# HighVBoard_2_0.net
KiCad netlist of a schematic drawn in EAGLE
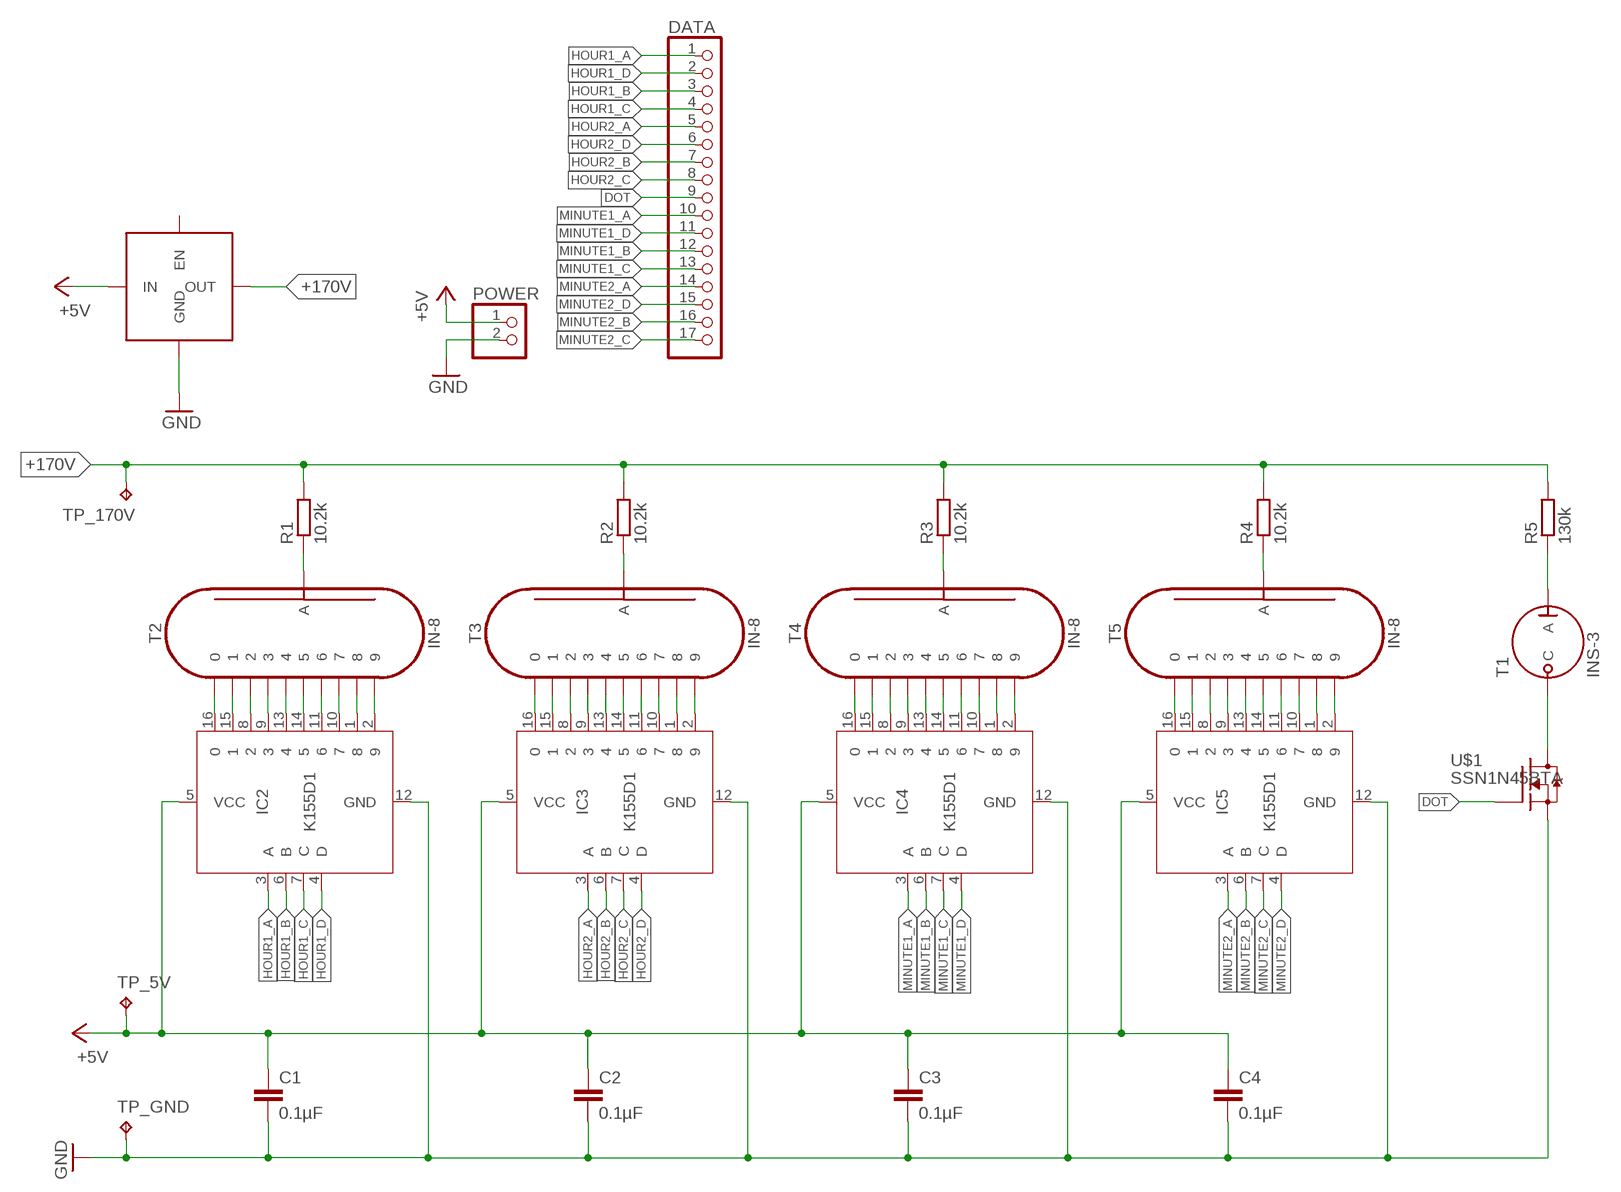
[diagram p0: schematic, sheet 1]

(export (version "E")
  (design (tool "Eeschema 10.0.6"))
  (components
    (comp (ref "C1")
      (value "0.1µF")
      (footprint "eagle-import:C025-024X044")
      (libsource (lib "eagle-import") (part "C-EU025-024X044"))
    )
    (comp (ref "C2")
      (value "0.1µF")
      (footprint "eagle-import:C025-024X044")
      (libsource (lib "eagle-import") (part "C-EU025-024X044"))
    )
    (comp (ref "C3")
      (value "0.1µF")
      (footprint "eagle-import:C025-024X044")
      (libsource (lib "eagle-import") (part "C-EU025-024X044"))
    )
    (comp (ref "C4")
      (value "0.1µF")
      (footprint "eagle-import:C025-024X044")
      (libsource (lib "eagle-import") (part "C-EU025-024X044"))
    )
    (comp (ref "DATA")
      (value "PINHD-1X17")
      (footprint "eagle-import:1X17")
      (libsource (lib "eagle-import") (part "PINHD-1X17"))
    )
    (comp (ref "IC2")
      (value "K155D1")
      (footprint "eagle-import:DIL16")
      (libsource (lib "eagle-import") (part "K155D1"))
    )
    (comp (ref "IC3")
      (value "K155D1")
      (footprint "eagle-import:DIL16")
      (libsource (lib "eagle-import") (part "K155D1"))
    )
    (comp (ref "IC4")
      (value "K155D1")
      (footprint "eagle-import:DIL16")
      (libsource (lib "eagle-import") (part "K155D1"))
    )
    (comp (ref "IC5")
      (value "K155D1")
      (footprint "eagle-import:DIL16")
      (libsource (lib "eagle-import") (part "K155D1"))
    )
    (comp (ref "POWER")
      (value "PINHD-1X2")
      (footprint "eagle-import:1X02")
      (libsource (lib "eagle-import") (part "PINHD-1X2"))
    )
    (comp (ref "R1")
      (value "10.2k")
      (footprint "eagle-import:0207_10")
      (libsource (lib "eagle-import") (part "R-EU_0207/10"))
    )
    (comp (ref "R2")
      (value "10.2k")
      (footprint "eagle-import:0207_10")
      (libsource (lib "eagle-import") (part "R-EU_0207/10"))
    )
    (comp (ref "R3")
      (value "10.2k")
      (footprint "eagle-import:0207_10")
      (libsource (lib "eagle-import") (part "R-EU_0207/10"))
    )
    (comp (ref "R4")
      (value "10.2k")
      (footprint "eagle-import:0207_10")
      (libsource (lib "eagle-import") (part "R-EU_0207/10"))
    )
    (comp (ref "R5")
      (value "130k")
      (footprint "eagle-import:0207_10")
      (libsource (lib "eagle-import") (part "R-EU_0207/10"))
    )
    (comp (ref "T1")
      (value "INS-3")
      (footprint "eagle-import:INS-3")
      (libsource (lib "eagle-import") (part "INS-3"))
    )
    (comp (ref "T2")
      (value "IN-8")
      (footprint "eagle-import:IN-8")
      (libsource (lib "eagle-import") (part "IN-8"))
    )
    (comp (ref "T3")
      (value "IN-8")
      (footprint "eagle-import:IN-8")
      (libsource (lib "eagle-import") (part "IN-8"))
    )
    (comp (ref "T4")
      (value "IN-8")
      (footprint "eagle-import:IN-8")
      (libsource (lib "eagle-import") (part "IN-8"))
    )
    (comp (ref "T5")
      (value "IN-8")
      (footprint "eagle-import:IN-8")
      (libsource (lib "eagle-import") (part "IN-8"))
    )
    (comp (ref "TP_5V")
      (value "TPPAD1-13")
      (footprint "eagle-import:P1-13")
      (libsource (lib "eagle-import") (part "TPPAD1-13"))
    )
    (comp (ref "TP_170V")
      (value "TPPAD1-13")
      (footprint "eagle-import:P1-13")
      (libsource (lib "eagle-import") (part "TPPAD1-13"))
    )
    (comp (ref "TP_GND")
      (value "TPPAD1-13")
      (footprint "eagle-import:P1-13")
      (libsource (lib "eagle-import") (part "TPPAD1-13"))
    )
    (comp (ref "U$1")
      (value "SSN1N45BTA")
      (footprint "eagle-import:TO92")
      (libsource (lib "eagle-import") (part "SSN1N45BTA"))
    )
    (comp (ref "U$2")
      (value "NIXIE-PSU")
      (footprint "eagle-import:NIXIE-PSU")
      (libsource (lib "eagle-import") (part "NIXIE-PSU"))
    )
  )
  (nets
    (net (code "1") (name "+5V") (class "Default")
      (node (ref "C1") (pin "1") (pinfunction "1_1") (pintype "passive"))
      (node (ref "C2") (pin "1") (pinfunction "1_1") (pintype "passive"))
      (node (ref "C3") (pin "1") (pinfunction "1_1") (pintype "passive"))
      (node (ref "C4") (pin "1") (pinfunction "1_1") (pintype "passive"))
      (node (ref "IC2") (pin "5") (pinfunction "VCC_5") (pintype "bidirectional"))
      (node (ref "IC3") (pin "5") (pinfunction "VCC_5") (pintype "bidirectional"))
      (node (ref "IC4") (pin "5") (pinfunction "VCC_5") (pintype "bidirectional"))
      (node (ref "IC5") (pin "5") (pinfunction "VCC_5") (pintype "bidirectional"))
      (node (ref "POWER") (pin "1") (pinfunction "1_1") (pintype "passive"))
      (node (ref "TP_5V") (pin "TP") (pinfunction "TP_TP") (pintype "input"))
      (node (ref "U$2") (pin "1") (pinfunction "IN_1") (pintype "bidirectional"))
    )
    (net (code "2") (name "+170V") (class "Default")
      (node (ref "R1") (pin "2") (pinfunction "2_2") (pintype "passive"))
      (node (ref "R2") (pin "2") (pinfunction "2_2") (pintype "passive"))
      (node (ref "R3") (pin "2") (pinfunction "2_2") (pintype "passive"))
      (node (ref "R4") (pin "2") (pinfunction "2_2") (pintype "passive"))
      (node (ref "R5") (pin "2") (pinfunction "2_2") (pintype "passive"))
      (node (ref "TP_170V") (pin "TP") (pinfunction "TP_TP") (pintype "input"))
      (node (ref "U$2") (pin "5") (pinfunction "OUT_5") (pintype "bidirectional"))
    )
    (net (code "3") (name "DOT") (class "Default")
      (node (ref "DATA") (pin "9") (pinfunction "9_9") (pintype "passive"))
      (node (ref "U$1") (pin "1") (pinfunction "G_1") (pintype "passive"))
    )
    (net (code "4") (name "GND") (class "Default")
      (node (ref "C1") (pin "2") (pinfunction "2_2") (pintype "passive"))
      (node (ref "C2") (pin "2") (pinfunction "2_2") (pintype "passive"))
      (node (ref "C3") (pin "2") (pinfunction "2_2") (pintype "passive"))
      (node (ref "C4") (pin "2") (pinfunction "2_2") (pintype "passive"))
      (node (ref "IC2") (pin "12") (pinfunction "GND_12") (pintype "bidirectional"))
      (node (ref "IC3") (pin "12") (pinfunction "GND_12") (pintype "bidirectional"))
      (node (ref "IC4") (pin "12") (pinfunction "GND_12") (pintype "bidirectional"))
      (node (ref "IC5") (pin "12") (pinfunction "GND_12") (pintype "bidirectional"))
      (node (ref "POWER") (pin "2") (pinfunction "2_2") (pintype "passive"))
      (node (ref "TP_GND") (pin "TP") (pinfunction "TP_TP") (pintype "input"))
      (node (ref "U$1") (pin "3") (pinfunction "S_3") (pintype "passive"))
      (node (ref "U$2") (pin "2") (pinfunction "GND_2") (pintype "bidirectional"))
      (node (ref "U$2") (pin "4") (pinfunction "GND_4") (pintype "bidirectional"))
    )
    (net (code "5") (name "HOUR1_A") (class "Default")
      (node (ref "DATA") (pin "1") (pinfunction "1_1") (pintype "passive"))
      (node (ref "IC2") (pin "3") (pinfunction "A_3") (pintype "bidirectional"))
    )
    (net (code "6") (name "HOUR1_B") (class "Default")
      (node (ref "DATA") (pin "3") (pinfunction "3_3") (pintype "passive"))
      (node (ref "IC2") (pin "6") (pinfunction "B_6") (pintype "bidirectional"))
    )
    (net (code "7") (name "HOUR1_C") (class "Default")
      (node (ref "DATA") (pin "4") (pinfunction "4_4") (pintype "passive"))
      (node (ref "IC2") (pin "7") (pinfunction "C_7") (pintype "bidirectional"))
    )
    (net (code "8") (name "HOUR1_D") (class "Default")
      (node (ref "DATA") (pin "2") (pinfunction "2_2") (pintype "passive"))
      (node (ref "IC2") (pin "4") (pinfunction "D_4") (pintype "bidirectional"))
    )
    (net (code "9") (name "HOUR2_A") (class "Default")
      (node (ref "DATA") (pin "5") (pinfunction "5_5") (pintype "passive"))
      (node (ref "IC3") (pin "3") (pinfunction "A_3") (pintype "bidirectional"))
    )
    (net (code "10") (name "HOUR2_B") (class "Default")
      (node (ref "DATA") (pin "7") (pinfunction "7_7") (pintype "passive"))
      (node (ref "IC3") (pin "6") (pinfunction "B_6") (pintype "bidirectional"))
    )
    (net (code "11") (name "HOUR2_C") (class "Default")
      (node (ref "DATA") (pin "8") (pinfunction "8_8") (pintype "passive"))
      (node (ref "IC3") (pin "7") (pinfunction "C_7") (pintype "bidirectional"))
    )
    (net (code "12") (name "HOUR2_D") (class "Default")
      (node (ref "DATA") (pin "6") (pinfunction "6_6") (pintype "passive"))
      (node (ref "IC3") (pin "4") (pinfunction "D_4") (pintype "bidirectional"))
    )
    (net (code "13") (name "MINUTE1_A") (class "Default")
      (node (ref "DATA") (pin "10") (pinfunction "10_10") (pintype "passive"))
      (node (ref "IC4") (pin "3") (pinfunction "A_3") (pintype "bidirectional"))
    )
    (net (code "14") (name "MINUTE1_B") (class "Default")
      (node (ref "DATA") (pin "12") (pinfunction "12_12") (pintype "passive"))
      (node (ref "IC4") (pin "6") (pinfunction "B_6") (pintype "bidirectional"))
    )
    (net (code "15") (name "MINUTE1_C") (class "Default")
      (node (ref "DATA") (pin "13") (pinfunction "13_13") (pintype "passive"))
      (node (ref "IC4") (pin "7") (pinfunction "C_7") (pintype "bidirectional"))
    )
    (net (code "16") (name "MINUTE1_D") (class "Default")
      (node (ref "DATA") (pin "11") (pinfunction "11_11") (pintype "passive"))
      (node (ref "IC4") (pin "4") (pinfunction "D_4") (pintype "bidirectional"))
    )
    (net (code "17") (name "MINUTE2_A") (class "Default")
      (node (ref "DATA") (pin "14") (pinfunction "14_14") (pintype "passive"))
      (node (ref "IC5") (pin "3") (pinfunction "A_3") (pintype "bidirectional"))
    )
    (net (code "18") (name "MINUTE2_B") (class "Default")
      (node (ref "DATA") (pin "16") (pinfunction "16_16") (pintype "passive"))
      (node (ref "IC5") (pin "6") (pinfunction "B_6") (pintype "bidirectional"))
    )
    (net (code "19") (name "MINUTE2_C") (class "Default")
      (node (ref "DATA") (pin "17") (pinfunction "17_17") (pintype "passive"))
      (node (ref "IC5") (pin "7") (pinfunction "C_7") (pintype "bidirectional"))
    )
    (net (code "20") (name "MINUTE2_D") (class "Default")
      (node (ref "DATA") (pin "15") (pinfunction "15_15") (pintype "passive"))
      (node (ref "IC5") (pin "4") (pinfunction "D_4") (pintype "bidirectional"))
    )
    (net (code "21") (name "Net-(IC2-0)") (class "Default")
      (node (ref "IC2") (pin "16") (pinfunction "0_16") (pintype "bidirectional"))
      (node (ref "T2") (pin "10") (pinfunction "0_10") (pintype "bidirectional"))
    )
    (net (code "22") (name "Net-(IC2-1)") (class "Default")
      (node (ref "IC2") (pin "15") (pinfunction "1_15") (pintype "bidirectional"))
      (node (ref "T2") (pin "1") (pinfunction "1_1") (pintype "bidirectional"))
    )
    (net (code "23") (name "Net-(IC2-2)") (class "Default")
      (node (ref "IC2") (pin "8") (pinfunction "2_8") (pintype "bidirectional"))
      (node (ref "T2") (pin "2") (pinfunction "2_2") (pintype "bidirectional"))
    )
    (net (code "24") (name "Net-(IC2-3)") (class "Default")
      (node (ref "IC2") (pin "9") (pinfunction "3_9") (pintype "bidirectional"))
      (node (ref "T2") (pin "3") (pinfunction "3_3") (pintype "bidirectional"))
    )
    (net (code "25") (name "Net-(IC2-4)") (class "Default")
      (node (ref "IC2") (pin "13") (pinfunction "4_13") (pintype "bidirectional"))
      (node (ref "T2") (pin "4") (pinfunction "4_4") (pintype "bidirectional"))
    )
    (net (code "26") (name "Net-(IC2-5)") (class "Default")
      (node (ref "IC2") (pin "14") (pinfunction "5_14") (pintype "bidirectional"))
      (node (ref "T2") (pin "5") (pinfunction "5_5") (pintype "bidirectional"))
    )
    (net (code "27") (name "Net-(IC2-6)") (class "Default")
      (node (ref "IC2") (pin "11") (pinfunction "6_11") (pintype "bidirectional"))
      (node (ref "T2") (pin "6") (pinfunction "6_6") (pintype "bidirectional"))
    )
    (net (code "28") (name "Net-(IC2-7)") (class "Default")
      (node (ref "IC2") (pin "10") (pinfunction "7_10") (pintype "bidirectional"))
      (node (ref "T2") (pin "7") (pinfunction "7_7") (pintype "bidirectional"))
    )
    (net (code "29") (name "Net-(IC2-8)") (class "Default")
      (node (ref "IC2") (pin "1") (pinfunction "8_1") (pintype "bidirectional"))
      (node (ref "T2") (pin "8") (pinfunction "8_8") (pintype "bidirectional"))
    )
    (net (code "30") (name "Net-(IC2-9)") (class "Default")
      (node (ref "IC2") (pin "2") (pinfunction "9_2") (pintype "bidirectional"))
      (node (ref "T2") (pin "9") (pinfunction "9_9") (pintype "bidirectional"))
    )
    (net (code "31") (name "Net-(IC3-0)") (class "Default")
      (node (ref "IC3") (pin "16") (pinfunction "0_16") (pintype "bidirectional"))
      (node (ref "T3") (pin "10") (pinfunction "0_10") (pintype "bidirectional"))
    )
    (net (code "32") (name "Net-(IC3-1)") (class "Default")
      (node (ref "IC3") (pin "15") (pinfunction "1_15") (pintype "bidirectional"))
      (node (ref "T3") (pin "1") (pinfunction "1_1") (pintype "bidirectional"))
    )
    (net (code "33") (name "Net-(IC3-2)") (class "Default")
      (node (ref "IC3") (pin "8") (pinfunction "2_8") (pintype "bidirectional"))
      (node (ref "T3") (pin "2") (pinfunction "2_2") (pintype "bidirectional"))
    )
    (net (code "34") (name "Net-(IC3-3)") (class "Default")
      (node (ref "IC3") (pin "9") (pinfunction "3_9") (pintype "bidirectional"))
      (node (ref "T3") (pin "3") (pinfunction "3_3") (pintype "bidirectional"))
    )
    (net (code "35") (name "Net-(IC3-4)") (class "Default")
      (node (ref "IC3") (pin "13") (pinfunction "4_13") (pintype "bidirectional"))
      (node (ref "T3") (pin "4") (pinfunction "4_4") (pintype "bidirectional"))
    )
    (net (code "36") (name "Net-(IC3-5)") (class "Default")
      (node (ref "IC3") (pin "14") (pinfunction "5_14") (pintype "bidirectional"))
      (node (ref "T3") (pin "5") (pinfunction "5_5") (pintype "bidirectional"))
    )
    (net (code "37") (name "Net-(IC3-6)") (class "Default")
      (node (ref "IC3") (pin "11") (pinfunction "6_11") (pintype "bidirectional"))
      (node (ref "T3") (pin "6") (pinfunction "6_6") (pintype "bidirectional"))
    )
    (net (code "38") (name "Net-(IC3-7)") (class "Default")
      (node (ref "IC3") (pin "10") (pinfunction "7_10") (pintype "bidirectional"))
      (node (ref "T3") (pin "7") (pinfunction "7_7") (pintype "bidirectional"))
    )
    (net (code "39") (name "Net-(IC3-8)") (class "Default")
      (node (ref "IC3") (pin "1") (pinfunction "8_1") (pintype "bidirectional"))
      (node (ref "T3") (pin "8") (pinfunction "8_8") (pintype "bidirectional"))
    )
    (net (code "40") (name "Net-(IC3-9)") (class "Default")
      (node (ref "IC3") (pin "2") (pinfunction "9_2") (pintype "bidirectional"))
      (node (ref "T3") (pin "9") (pinfunction "9_9") (pintype "bidirectional"))
    )
    (net (code "41") (name "Net-(IC4-0)") (class "Default")
      (node (ref "IC4") (pin "16") (pinfunction "0_16") (pintype "bidirectional"))
      (node (ref "T4") (pin "10") (pinfunction "0_10") (pintype "bidirectional"))
    )
    (net (code "42") (name "Net-(IC4-1)") (class "Default")
      (node (ref "IC4") (pin "15") (pinfunction "1_15") (pintype "bidirectional"))
      (node (ref "T4") (pin "1") (pinfunction "1_1") (pintype "bidirectional"))
    )
    (net (code "43") (name "Net-(IC4-2)") (class "Default")
      (node (ref "IC4") (pin "8") (pinfunction "2_8") (pintype "bidirectional"))
      (node (ref "T4") (pin "2") (pinfunction "2_2") (pintype "bidirectional"))
    )
    (net (code "44") (name "Net-(IC4-3)") (class "Default")
      (node (ref "IC4") (pin "9") (pinfunction "3_9") (pintype "bidirectional"))
      (node (ref "T4") (pin "3") (pinfunction "3_3") (pintype "bidirectional"))
    )
    (net (code "45") (name "Net-(IC4-4)") (class "Default")
      (node (ref "IC4") (pin "13") (pinfunction "4_13") (pintype "bidirectional"))
      (node (ref "T4") (pin "4") (pinfunction "4_4") (pintype "bidirectional"))
    )
    (net (code "46") (name "Net-(IC4-5)") (class "Default")
      (node (ref "IC4") (pin "14") (pinfunction "5_14") (pintype "bidirectional"))
      (node (ref "T4") (pin "5") (pinfunction "5_5") (pintype "bidirectional"))
    )
    (net (code "47") (name "Net-(IC4-6)") (class "Default")
      (node (ref "IC4") (pin "11") (pinfunction "6_11") (pintype "bidirectional"))
      (node (ref "T4") (pin "6") (pinfunction "6_6") (pintype "bidirectional"))
    )
    (net (code "48") (name "Net-(IC4-7)") (class "Default")
      (node (ref "IC4") (pin "10") (pinfunction "7_10") (pintype "bidirectional"))
      (node (ref "T4") (pin "7") (pinfunction "7_7") (pintype "bidirectional"))
    )
    (net (code "49") (name "Net-(IC4-8)") (class "Default")
      (node (ref "IC4") (pin "1") (pinfunction "8_1") (pintype "bidirectional"))
      (node (ref "T4") (pin "8") (pinfunction "8_8") (pintype "bidirectional"))
    )
    (net (code "50") (name "Net-(IC4-9)") (class "Default")
      (node (ref "IC4") (pin "2") (pinfunction "9_2") (pintype "bidirectional"))
      (node (ref "T4") (pin "9") (pinfunction "9_9") (pintype "bidirectional"))
    )
    (net (code "51") (name "Net-(IC5-0)") (class "Default")
      (node (ref "IC5") (pin "16") (pinfunction "0_16") (pintype "bidirectional"))
      (node (ref "T5") (pin "10") (pinfunction "0_10") (pintype "bidirectional"))
    )
    (net (code "52") (name "Net-(IC5-1)") (class "Default")
      (node (ref "IC5") (pin "15") (pinfunction "1_15") (pintype "bidirectional"))
      (node (ref "T5") (pin "1") (pinfunction "1_1") (pintype "bidirectional"))
    )
    (net (code "53") (name "Net-(IC5-2)") (class "Default")
      (node (ref "IC5") (pin "8") (pinfunction "2_8") (pintype "bidirectional"))
      (node (ref "T5") (pin "2") (pinfunction "2_2") (pintype "bidirectional"))
    )
    (net (code "54") (name "Net-(IC5-3)") (class "Default")
      (node (ref "IC5") (pin "9") (pinfunction "3_9") (pintype "bidirectional"))
      (node (ref "T5") (pin "3") (pinfunction "3_3") (pintype "bidirectional"))
    )
    (net (code "55") (name "Net-(IC5-4)") (class "Default")
      (node (ref "IC5") (pin "13") (pinfunction "4_13") (pintype "bidirectional"))
      (node (ref "T5") (pin "4") (pinfunction "4_4") (pintype "bidirectional"))
    )
    (net (code "56") (name "Net-(IC5-5)") (class "Default")
      (node (ref "IC5") (pin "14") (pinfunction "5_14") (pintype "bidirectional"))
      (node (ref "T5") (pin "5") (pinfunction "5_5") (pintype "bidirectional"))
    )
    (net (code "57") (name "Net-(IC5-6)") (class "Default")
      (node (ref "IC5") (pin "11") (pinfunction "6_11") (pintype "bidirectional"))
      (node (ref "T5") (pin "6") (pinfunction "6_6") (pintype "bidirectional"))
    )
    (net (code "58") (name "Net-(IC5-7)") (class "Default")
      (node (ref "IC5") (pin "10") (pinfunction "7_10") (pintype "bidirectional"))
      (node (ref "T5") (pin "7") (pinfunction "7_7") (pintype "bidirectional"))
    )
    (net (code "59") (name "Net-(IC5-8)") (class "Default")
      (node (ref "IC5") (pin "1") (pinfunction "8_1") (pintype "bidirectional"))
      (node (ref "T5") (pin "8") (pinfunction "8_8") (pintype "bidirectional"))
    )
    (net (code "60") (name "Net-(IC5-9)") (class "Default")
      (node (ref "IC5") (pin "2") (pinfunction "9_2") (pintype "bidirectional"))
      (node (ref "T5") (pin "9") (pinfunction "9_9") (pintype "bidirectional"))
    )
    (net (code "61") (name "Net-(R1-Pad1)") (class "Default")
      (node (ref "R1") (pin "1") (pinfunction "1_1") (pintype "passive"))
      (node (ref "T2") (pin "A") (pinfunction "A_A") (pintype "bidirectional"))
    )
    (net (code "62") (name "Net-(R2-Pad1)") (class "Default")
      (node (ref "R2") (pin "1") (pinfunction "1_1") (pintype "passive"))
      (node (ref "T3") (pin "A") (pinfunction "A_A") (pintype "bidirectional"))
    )
    (net (code "63") (name "Net-(R3-Pad1)") (class "Default")
      (node (ref "R3") (pin "1") (pinfunction "1_1") (pintype "passive"))
      (node (ref "T4") (pin "A") (pinfunction "A_A") (pintype "bidirectional"))
    )
    (net (code "64") (name "Net-(R4-Pad1)") (class "Default")
      (node (ref "R4") (pin "1") (pinfunction "1_1") (pintype "passive"))
      (node (ref "T5") (pin "A") (pinfunction "A_A") (pintype "bidirectional"))
    )
    (net (code "65") (name "Net-(R5-Pad1)") (class "Default")
      (node (ref "R5") (pin "1") (pinfunction "1_1") (pintype "passive"))
      (node (ref "T1") (pin "A") (pinfunction "A_A") (pintype "bidirectional"))
    )
    (net (code "66") (name "Net-(U$1-D)") (class "Default")
      (node (ref "T1") (pin "C") (pinfunction "C_C") (pintype "bidirectional"))
      (node (ref "U$1") (pin "2") (pinfunction "D_2") (pintype "passive"))
    )
    (net (code "67") (name "unconnected-(U$2-EN-Pad3)") (class "Default")
      (node (ref "U$2") (pin "3") (pinfunction "EN_3") (pintype "bidirectional"))
    )
  )
)
